# Memory.net
KiCad netlist of a schematic drawn in Altium Designer
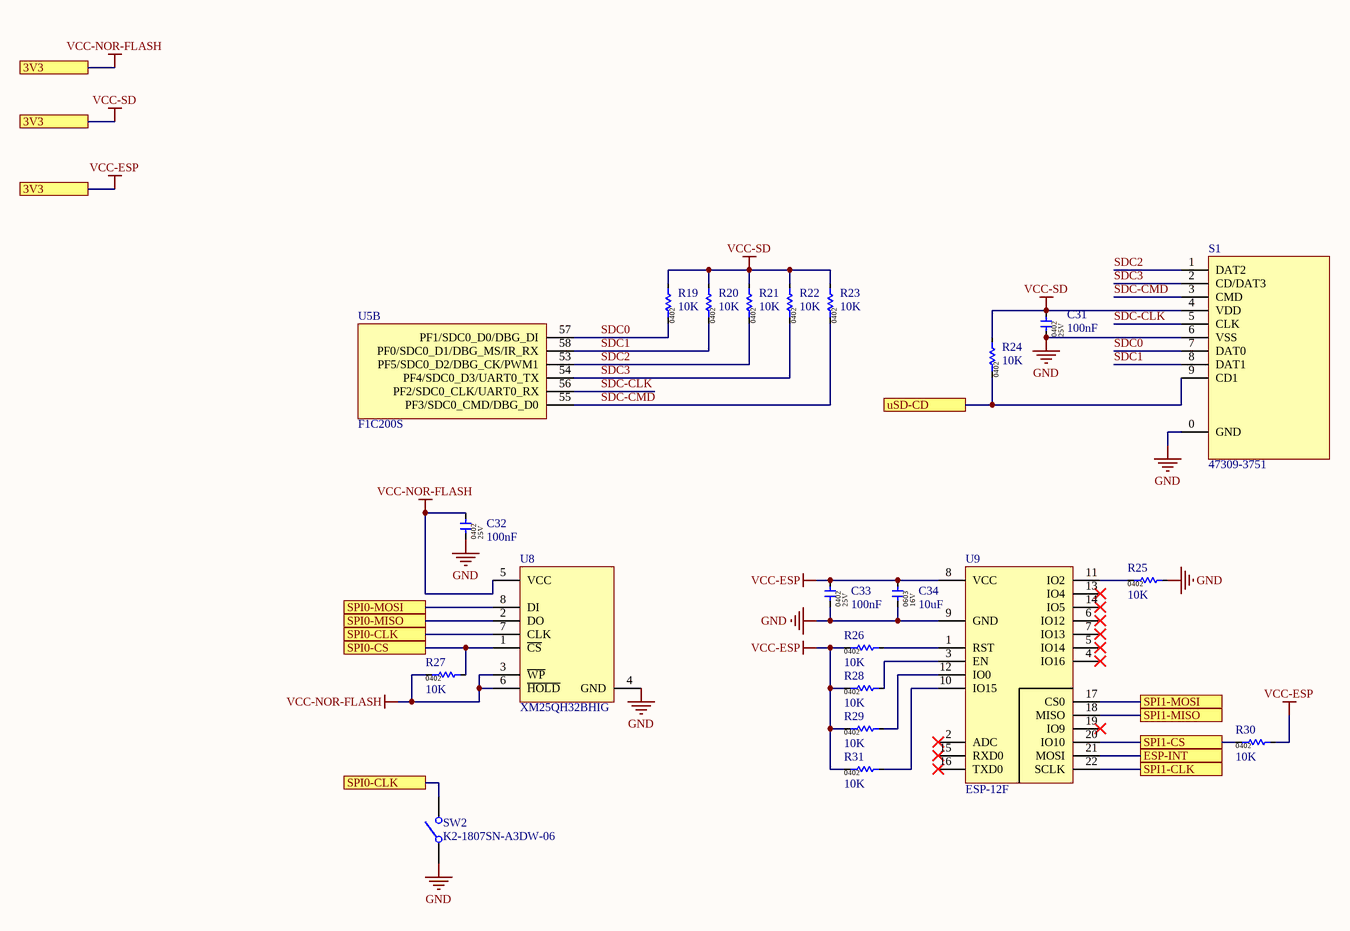
[diagram p0: Memory.SchDoc]

(export (version "E")
  (design (tool "Eeschema 10.0.6"))
  (components
    (comp (ref "C31")
      (value "100nF")
      (footprint "CAP-0402")
      (description "100nF ±10% 25V X5R 0402 Multilayer Ceramic Capacitors MLCC - SMD/SMT RoHS")
      (fields (field (name "MANUFACTURE PART") "0402X104K250CT") (field (name "VOLTAGE") "25V"))
      (libsource (lib "Capacitor Database") (part "Cap-non-polarized"))
    )
    (comp (ref "C32")
      (value "100nF")
      (footprint "CAP-0402")
      (description "100nF ±10% 25V X5R 0402 Multilayer Ceramic Capacitors MLCC - SMD/SMT RoHS")
      (fields (field (name "MANUFACTURE PART") "0402X104K250CT") (field (name "VOLTAGE") "25V"))
      (libsource (lib "Capacitor Database") (part "Cap-non-polarized"))
    )
    (comp (ref "C33")
      (value "100nF")
      (footprint "CAP-0402")
      (description "100nF ±10% 25V X5R 0402 Multilayer Ceramic Capacitors MLCC - SMD/SMT RoHS")
      (fields (field (name "MANUFACTURE PART") "0402X104K250CT") (field (name "VOLTAGE") "25V"))
      (libsource (lib "Capacitor Database") (part "Cap-non-polarized"))
    )
    (comp (ref "C34")
      (value "10uF")
      (footprint "CAP-0603")
      (description "16V 10uF X5R ±20% 0603 Multilayer Ceramic Capacitors MLCC - SMD/SMT ROHS")
      (fields (field (name "MANUFACTURE PART") "0603X106M160CT") (field (name "VOLTAGE") "16V"))
      (libsource (lib "Capacitor Database") (part "Cap-non-polarized"))
    )
    (comp (ref "R19")
      (value "10K")
      (footprint "RES-0402")
      (description "10kΩ ±1% 1/16W ±100ppm/℃ 0402 Chip Resistor - Surface Mount RoHS")
      (fields (field (name "MANUFACTURE PART") "WR04X1002FTL"))
      (libsource (lib "Resistor Database") (part "Resistor"))
    )
    (comp (ref "R20")
      (value "10K")
      (footprint "RES-0402")
      (description "10kΩ ±1% 1/16W ±100ppm/℃ 0402 Chip Resistor - Surface Mount RoHS")
      (fields (field (name "MANUFACTURE PART") "WR04X1002FTL"))
      (libsource (lib "Resistor Database") (part "Resistor"))
    )
    (comp (ref "R21")
      (value "10K")
      (footprint "RES-0402")
      (description "10kΩ ±1% 1/16W ±100ppm/℃ 0402 Chip Resistor - Surface Mount RoHS")
      (fields (field (name "MANUFACTURE PART") "WR04X1002FTL"))
      (libsource (lib "Resistor Database") (part "Resistor"))
    )
    (comp (ref "R22")
      (value "10K")
      (footprint "RES-0402")
      (description "10kΩ ±1% 1/16W ±100ppm/℃ 0402 Chip Resistor - Surface Mount RoHS")
      (fields (field (name "MANUFACTURE PART") "WR04X1002FTL"))
      (libsource (lib "Resistor Database") (part "Resistor"))
    )
    (comp (ref "R23")
      (value "10K")
      (footprint "RES-0402")
      (description "10kΩ ±1% 1/16W ±100ppm/℃ 0402 Chip Resistor - Surface Mount RoHS")
      (fields (field (name "MANUFACTURE PART") "WR04X1002FTL"))
      (libsource (lib "Resistor Database") (part "Resistor"))
    )
    (comp (ref "R24")
      (value "10K")
      (footprint "RES-0402")
      (description "10kΩ ±1% 1/16W ±100ppm/℃ 0402 Chip Resistor - Surface Mount RoHS")
      (fields (field (name "MANUFACTURE PART") "WR04X1002FTL"))
      (libsource (lib "Resistor Database") (part "Resistor"))
    )
    (comp (ref "R25")
      (value "10K")
      (footprint "RES-0402")
      (description "10kΩ ±1% 1/16W ±100ppm/℃ 0402 Chip Resistor - Surface Mount RoHS")
      (fields (field (name "MANUFACTURE PART") "WR04X1002FTL"))
      (libsource (lib "Resistor Database") (part "Resistor"))
    )
    (comp (ref "R26")
      (value "10K")
      (footprint "RES-0402")
      (description "10kΩ ±1% 1/16W ±100ppm/℃ 0402 Chip Resistor - Surface Mount RoHS")
      (fields (field (name "MANUFACTURE PART") "WR04X1002FTL"))
      (libsource (lib "Resistor Database") (part "Resistor"))
    )
    (comp (ref "R27")
      (value "10K")
      (footprint "RES-0402")
      (description "10kΩ ±1% 1/16W ±100ppm/℃ 0402 Chip Resistor - Surface Mount RoHS")
      (fields (field (name "MANUFACTURE PART") "WR04X1002FTL"))
      (libsource (lib "Resistor Database") (part "Resistor"))
    )
    (comp (ref "R28")
      (value "10K")
      (footprint "RES-0402")
      (description "10kΩ ±1% 1/16W ±100ppm/℃ 0402 Chip Resistor - Surface Mount RoHS")
      (fields (field (name "MANUFACTURE PART") "WR04X1002FTL"))
      (libsource (lib "Resistor Database") (part "Resistor"))
    )
    (comp (ref "R29")
      (value "10K")
      (footprint "RES-0402")
      (description "10kΩ ±1% 1/16W ±100ppm/℃ 0402 Chip Resistor - Surface Mount RoHS")
      (fields (field (name "MANUFACTURE PART") "WR04X1002FTL"))
      (libsource (lib "Resistor Database") (part "Resistor"))
    )
    (comp (ref "R30")
      (value "10K")
      (footprint "RES-0402")
      (description "10kΩ ±1% 1/16W ±100ppm/℃ 0402 Chip Resistor - Surface Mount RoHS")
      (fields (field (name "MANUFACTURE PART") "WR04X1002FTL"))
      (libsource (lib "Resistor Database") (part "Resistor"))
    )
    (comp (ref "R31")
      (value "10K")
      (footprint "RES-0402")
      (description "10kΩ ±1% 1/16W ±100ppm/℃ 0402 Chip Resistor - Surface Mount RoHS")
      (fields (field (name "MANUFACTURE PART") "WR04X1002FTL"))
      (libsource (lib "Resistor Database") (part "Resistor"))
    )
    (comp (ref "S1")
      (value "47309-3751")
      (footprint "Micro SDCARD short")
      (description "Short micro sd card 3.75H")
      (libsource (lib "Connectors, Misc") (part "micro SDCARD"))
    )
    (comp (ref "SW2")
      (value "K2-1807SN-A3DW-06")
      (footprint "SW - TYPE 3")
      (description "SMD,3×4×2.0mm Tactile Switches RoHS")
      (libsource (lib "Connectors, Misc") (part "Tactile Switch"))
    )
    (comp (ref "U5")
      (value "F1C200S")
      (footprint "F1Cx00s")
      (description "The Allwinner F1C200s is a small SoC with an ARM926EJ-S CPU core and 64MB of embedded DDR SDRAM.")
      (libsource (lib "IC Database") (part "F1CX00S"))
    )
    (comp (ref "U8")
      (value "XM25QH32BHIG")
      (footprint "SOP8-208mil")
      (description "32Mb (256 Bytes x 16384 pages) SPI - Dual/Quad I/O, QPI FLASH Non-Volatile SOP-8L NOR FLASH ROHS")
      (libsource (lib "IC Database") (part "NOR-FLASH"))
    )
    (comp (ref "U9")
      (value "ESP-12F")
      (footprint "ESP8266")
      (description "ESP8266 module")
      (libsource (lib "IC Database") (part "ESP8266-12E/F"))
    )
  )
  (nets
    (net (code "1") (name "/ESP-INT") (class "Default")
      (node (ref "U9") (pin "21") (pinfunction "MOSI_21") (pintype "passive"))
    )
    (net (code "2") (name "/SDC-CLK") (class "Default")
      (node (ref "S1") (pin "5") (pinfunction "CLK_5") (pintype "passive"))
      (node (ref "U5") (pin "56") (pinfunction "PF2/SDC0_CLK/UART0_RX_56") (pintype "passive"))
    )
    (net (code "3") (name "/SDC-CMD") (class "Default")
      (node (ref "R23") (pin "1") (pinfunction "1_1") (pintype "passive"))
      (node (ref "S1") (pin "3") (pinfunction "CMD_3") (pintype "passive"))
      (node (ref "U5") (pin "55") (pinfunction "PF3/SDC0_CMD/DBG_D0_55") (pintype "passive"))
    )
    (net (code "4") (name "/SDC0") (class "Default")
      (node (ref "R19") (pin "1") (pinfunction "1_1") (pintype "passive"))
      (node (ref "S1") (pin "7") (pinfunction "DAT0_7") (pintype "passive"))
      (node (ref "U5") (pin "57") (pinfunction "PF1/SDC0_D0/DBG_DI_57") (pintype "passive"))
    )
    (net (code "5") (name "/SDC1") (class "Default")
      (node (ref "R20") (pin "1") (pinfunction "1_1") (pintype "passive"))
      (node (ref "S1") (pin "8") (pinfunction "DAT1_8") (pintype "passive"))
      (node (ref "U5") (pin "58") (pinfunction "PF0/SDC0_D1/DBG_MS/IR_RX_58") (pintype "passive"))
    )
    (net (code "6") (name "/SDC2") (class "Default")
      (node (ref "R21") (pin "1") (pinfunction "1_1") (pintype "passive"))
      (node (ref "S1") (pin "1") (pinfunction "DAT2_1") (pintype "passive"))
      (node (ref "U5") (pin "53") (pinfunction "PF5/SDC0_D2/DBG_CK/PWM1_53") (pintype "passive"))
    )
    (net (code "7") (name "/SDC3") (class "Default")
      (node (ref "R22") (pin "1") (pinfunction "1_1") (pintype "passive"))
      (node (ref "S1") (pin "2") (pinfunction "CD/DAT3_2") (pintype "passive"))
      (node (ref "U5") (pin "54") (pinfunction "PF4/SDC0_D3/UART0_TX_54") (pintype "passive"))
    )
    (net (code "8") (name "/SPI0-CLK") (class "Default")
      (node (ref "SW2") (pin "2") (pintype "passive"))
      (node (ref "U8") (pin "7") (pinfunction "CLK_7") (pintype "passive"))
    )
    (net (code "9") (name "/SPI0-CS") (class "Default")
      (node (ref "R27") (pin "2") (pinfunction "2_2") (pintype "passive"))
      (node (ref "U8") (pin "1") (pinfunction "~{CS}_1") (pintype "passive"))
    )
    (net (code "10") (name "/SPI0-MISO") (class "Default")
      (node (ref "U8") (pin "2") (pinfunction "DO_2") (pintype "passive"))
    )
    (net (code "11") (name "/SPI0-MOSI") (class "Default")
      (node (ref "U8") (pin "8") (pinfunction "DI_8") (pintype "passive"))
    )
    (net (code "12") (name "/SPI1-CLK") (class "Default")
      (node (ref "U9") (pin "22") (pinfunction "SCLK_22") (pintype "passive"))
    )
    (net (code "13") (name "/SPI1-CS") (class "Default")
      (node (ref "R30") (pin "1") (pinfunction "1_1") (pintype "passive"))
      (node (ref "U9") (pin "20") (pinfunction "IO10_20") (pintype "passive"))
    )
    (net (code "14") (name "/SPI1-MISO") (class "Default")
      (node (ref "U9") (pin "18") (pinfunction "MISO_18") (pintype "passive"))
    )
    (net (code "15") (name "/SPI1-MOSI") (class "Default")
      (node (ref "U9") (pin "17") (pinfunction "CS0_17") (pintype "passive"))
    )
    (net (code "16") (name "/uSD-CD") (class "Default")
      (node (ref "R24") (pin "1") (pinfunction "1_1") (pintype "passive"))
      (node (ref "S1") (pin "9") (pinfunction "CD1_9") (pintype "passive"))
    )
    (net (code "17") (name "GND") (class "Default")
      (node (ref "C31") (pin "1") (pinfunction "1_1") (pintype "passive"))
      (node (ref "C32") (pin "1") (pinfunction "1_1") (pintype "passive"))
      (node (ref "C33") (pin "1") (pinfunction "1_1") (pintype "passive"))
      (node (ref "C34") (pin "1") (pinfunction "1_1") (pintype "passive"))
      (node (ref "R25") (pin "2") (pinfunction "2_2") (pintype "passive"))
      (node (ref "S1") (pin "0") (pinfunction "GND_0") (pintype "passive"))
      (node (ref "S1") (pin "6") (pinfunction "VSS_6") (pintype "passive"))
      (node (ref "SW2") (pin "1") (pintype "passive"))
      (node (ref "U8") (pin "4") (pinfunction "GND_4") (pintype "passive"))
      (node (ref "U9") (pin "9") (pinfunction "GND_9") (pintype "passive"))
    )
    (net (code "18") (name "Net-(U9-EN)") (class "Default")
      (node (ref "R28") (pin "2") (pinfunction "2_2") (pintype "passive"))
      (node (ref "U9") (pin "3") (pinfunction "EN_3") (pintype "passive"))
    )
    (net (code "19") (name "Net-(U9-IO0)") (class "Default")
      (node (ref "R29") (pin "2") (pinfunction "2_2") (pintype "passive"))
      (node (ref "U9") (pin "12") (pinfunction "IO0_12") (pintype "passive"))
    )
    (net (code "20") (name "Net-(U9-IO2)") (class "Default")
      (node (ref "R25") (pin "1") (pinfunction "1_1") (pintype "passive"))
      (node (ref "U9") (pin "11") (pinfunction "IO2_11") (pintype "passive"))
    )
    (net (code "21") (name "Net-(U9-IO15)") (class "Default")
      (node (ref "R31") (pin "2") (pinfunction "2_2") (pintype "passive"))
      (node (ref "U9") (pin "10") (pinfunction "IO15_10") (pintype "passive"))
    )
    (net (code "22") (name "Net-(U9-RST)") (class "Default")
      (node (ref "R26") (pin "2") (pinfunction "2_2") (pintype "passive"))
      (node (ref "U9") (pin "1") (pinfunction "RST_1") (pintype "passive"))
    )
    (net (code "23") (name "VCC-ESP") (class "Default")
      (node (ref "C31") (pin "2") (pinfunction "2_2") (pintype "passive"))
      (node (ref "C32") (pin "2") (pinfunction "2_2") (pintype "passive"))
      (node (ref "C33") (pin "2") (pinfunction "2_2") (pintype "passive"))
      (node (ref "C34") (pin "2") (pinfunction "2_2") (pintype "passive"))
      (node (ref "R19") (pin "2") (pinfunction "2_2") (pintype "passive"))
      (node (ref "R20") (pin "2") (pinfunction "2_2") (pintype "passive"))
      (node (ref "R21") (pin "2") (pinfunction "2_2") (pintype "passive"))
      (node (ref "R22") (pin "2") (pinfunction "2_2") (pintype "passive"))
      (node (ref "R23") (pin "2") (pinfunction "2_2") (pintype "passive"))
      (node (ref "R24") (pin "2") (pinfunction "2_2") (pintype "passive"))
      (node (ref "R26") (pin "1") (pinfunction "1_1") (pintype "passive"))
      (node (ref "R27") (pin "1") (pinfunction "1_1") (pintype "passive"))
      (node (ref "R28") (pin "1") (pinfunction "1_1") (pintype "passive"))
      (node (ref "R29") (pin "1") (pinfunction "1_1") (pintype "passive"))
      (node (ref "R30") (pin "2") (pinfunction "2_2") (pintype "passive"))
      (node (ref "R31") (pin "1") (pinfunction "1_1") (pintype "passive"))
      (node (ref "S1") (pin "4") (pinfunction "VDD_4") (pintype "passive"))
      (node (ref "U8") (pin "3") (pinfunction "~{WP}_3") (pintype "passive"))
      (node (ref "U8") (pin "5") (pinfunction "VCC_5") (pintype "passive"))
      (node (ref "U8") (pin "6") (pinfunction "~{HOLD}_6") (pintype "passive"))
      (node (ref "U9") (pin "8") (pinfunction "VCC_8") (pintype "passive"))
    )
    (net (code "24") (name "unconnected-(U9-ADC-Pad2)") (class "Default")
      (node (ref "U9") (pin "2") (pinfunction "ADC_2") (pintype "passive+no_connect"))
    )
    (net (code "25") (name "unconnected-(U9-IO4-Pad13)") (class "Default")
      (node (ref "U9") (pin "13") (pinfunction "IO4_13") (pintype "passive+no_connect"))
    )
    (net (code "26") (name "unconnected-(U9-IO5-Pad14)") (class "Default")
      (node (ref "U9") (pin "14") (pinfunction "IO5_14") (pintype "passive+no_connect"))
    )
    (net (code "27") (name "unconnected-(U9-IO9-Pad19)") (class "Default")
      (node (ref "U9") (pin "19") (pinfunction "IO9_19") (pintype "passive+no_connect"))
    )
    (net (code "28") (name "unconnected-(U9-IO12-Pad6)") (class "Default")
      (node (ref "U9") (pin "6") (pinfunction "IO12_6") (pintype "passive+no_connect"))
    )
    (net (code "29") (name "unconnected-(U9-IO13-Pad7)") (class "Default")
      (node (ref "U9") (pin "7") (pinfunction "IO13_7") (pintype "passive+no_connect"))
    )
    (net (code "30") (name "unconnected-(U9-IO14-Pad5)") (class "Default")
      (node (ref "U9") (pin "5") (pinfunction "IO14_5") (pintype "passive+no_connect"))
    )
    (net (code "31") (name "unconnected-(U9-IO16-Pad4)") (class "Default")
      (node (ref "U9") (pin "4") (pinfunction "IO16_4") (pintype "passive+no_connect"))
    )
    (net (code "32") (name "unconnected-(U9-RXD0-Pad15)") (class "Default")
      (node (ref "U9") (pin "15") (pinfunction "RXD0_15") (pintype "passive+no_connect"))
    )
    (net (code "33") (name "unconnected-(U9-TXD0-Pad16)") (class "Default")
      (node (ref "U9") (pin "16") (pinfunction "TXD0_16") (pintype "passive+no_connect"))
    )
  )
)
